# LineCliffSensors.net
KiCad netlist of a schematic drawn in Altium Designer
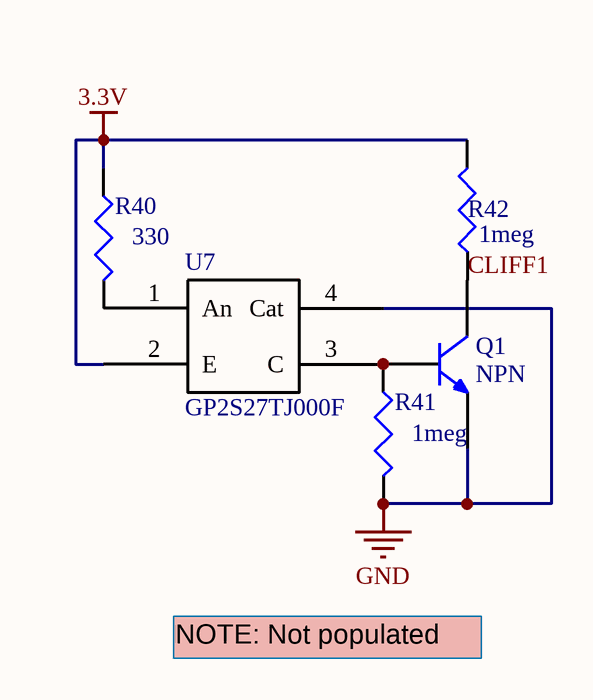
[diagram p0: LineCliffSensors.SchDoc]

(export (version "E")
  (design (tool "Eeschema 10.0.6"))
  (components
    (comp (ref "Q1") (value "NPN") (footprint "SOT-23") (libsource (lib "mrone") (part "NPN")))
    (comp (ref "R40")
      (value "330")
      (footprint "RESC1608L")
      (description "Resistor")
      (fields (field (name "Comment") "Res3") (field (name "PUBLISHER") "Altium Limited"))
      (libsource (lib "Miscellaneous Devices") (part "Res3"))
    )
    (comp (ref "R41")
      (value "1meg")
      (footprint "RESC1608L")
      (description "Resistor")
      (fields (field (name "Comment") "Res3") (field (name "PUBLISHER") "Altium Limited"))
      (libsource (lib "Miscellaneous Devices") (part "Res3"))
    )
    (comp (ref "R42")
      (value "1meg")
      (footprint "RESC1608L")
      (description "Resistor")
      (fields (field (name "Comment") "Res3") (field (name "PUBLISHER") "Altium Limited"))
      (libsource (lib "Miscellaneous Devices") (part "Res3"))
    )
    (comp (ref "U7")
      (value "GP2S27TJ000F")
      (footprint "GP2S27J0000F")
      (libsource (lib "mrone") (part "GP2S27TJ000F"))
    )
  )
  (nets
    (net (code "1") (name "/CLIFF1") (class "Default")
      (node (ref "Q1") (pin "3") (pinfunction "C_3") (pintype "passive"))
      (node (ref "R42") (pin "1") (pinfunction "1_1") (pintype "passive"))
    )
    (net (code "2") (name "3.3V") (class "Default")
      (node (ref "R40") (pin "1") (pinfunction "1_1") (pintype "passive"))
      (node (ref "R42") (pin "2") (pinfunction "2_2") (pintype "passive"))
      (node (ref "U7") (pin "2") (pinfunction "E_2") (pintype "passive"))
    )
    (net (code "3") (name "GND") (class "Default")
      (node (ref "Q1") (pin "2") (pinfunction "E_2") (pintype "passive"))
      (node (ref "R41") (pin "2") (pinfunction "2_2") (pintype "passive"))
      (node (ref "U7") (pin "4") (pinfunction "Cat_4") (pintype "passive"))
    )
    (net (code "4") (name "Net-(Q1-B)") (class "Default")
      (node (ref "Q1") (pin "1") (pinfunction "B_1") (pintype "passive"))
      (node (ref "R41") (pin "1") (pinfunction "1_1") (pintype "passive"))
      (node (ref "U7") (pin "3") (pinfunction "C_3") (pintype "passive"))
    )
    (net (code "5") (name "Net-(U7-An)") (class "Default")
      (node (ref "R40") (pin "2") (pinfunction "2_2") (pintype "passive"))
      (node (ref "U7") (pin "1") (pinfunction "An_1") (pintype "passive"))
    )
  )
)
